# POWER.net
KiCad netlist of a schematic drawn in Altium Designer
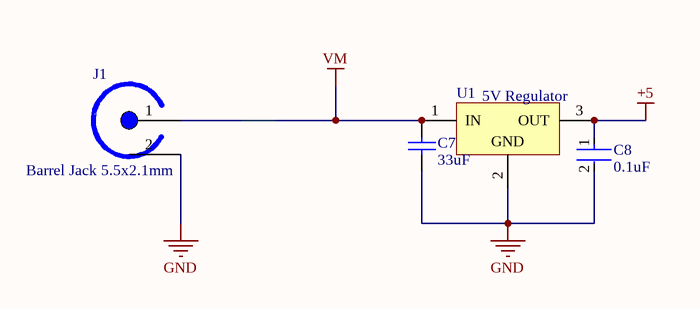
[diagram p0: POWER.SchDoc]

(export (version "E")
  (design (tool "Eeschema 10.0.6"))
  (components
    (comp (ref "C7")
      (value "33uF")
      (footprint "CAPC0805(2012)100_L")
      (description "CAP 330nF 25V -20% to +80% 0805 (2012 Metric) Thickness 1mm SMD")
      (fields (field (name "TOLERANCE") "-20% to +80%"))
      (libsource (lib "Altium Content Vault") (part "CAP"))
    )
    (comp (ref "C8")
      (value "0.1uF")
      (footprint "FP-0805B-IPC_C")
      (description "CAP CER 0.1UF 50V X7R 0805")
      (fields (field (name "VOLTAGE") "50V") (field (name "TOLERANCE") "10%"))
      (libsource (lib "Altium Content Vault") (part "02cd4be3c70576c341d710602a673aa"))
    )
    (comp (ref "J1")
      (value "Barrel Jack 5.5x2.1mm")
      (footprint "Barrel Jack 2.1x5.5mm THT")
      (description "GCT DCJ200-10-A-K1-K")
      (fields (field (name "SOURCE") "JCULibrary.SchLib"))
      (libsource (lib "James Cook University") (part "Barrel Jack 5.5x2.1mm"))
    )
    (comp (ref "U1")
      (value "5V Regulator")
      (footprint "TO220")
      (description "Positive Voltage Regulator, 5V, 3-Pin TO-220")
      (libsource (lib "Altium Content Vault") (part "PM-REG-L4940-SIL3"))
    )
  )
  (nets
    (net (code "1") (name "+5") (class "Default")
      (node (ref "C8") (pin "1") (pinfunction "1_1") (pintype "passive"))
      (node (ref "U1") (pin "3") (pinfunction "OUT_3") (pintype "power_in"))
    )
    (net (code "2") (name "GND") (class "Default")
      (node (ref "C7") (pin "1") (pinfunction "1_1") (pintype "passive"))
      (node (ref "C8") (pin "2") (pinfunction "2_2") (pintype "passive"))
      (node (ref "J1") (pin "2") (pinfunction "SLEEVE_2") (pintype "power_in"))
      (node (ref "U1") (pin "2") (pinfunction "GND_2") (pintype "power_in"))
    )
    (net (code "3") (name "VM") (class "Default")
      (node (ref "C7") (pin "2") (pinfunction "2_2") (pintype "passive"))
      (node (ref "J1") (pin "1") (pinfunction "TIP_1") (pintype "power_in"))
      (node (ref "U1") (pin "1") (pinfunction "IN_1") (pintype "power_in"))
    )
  )
)
